# POWER.net
KiCad netlist of a schematic drawn in Altium Designer
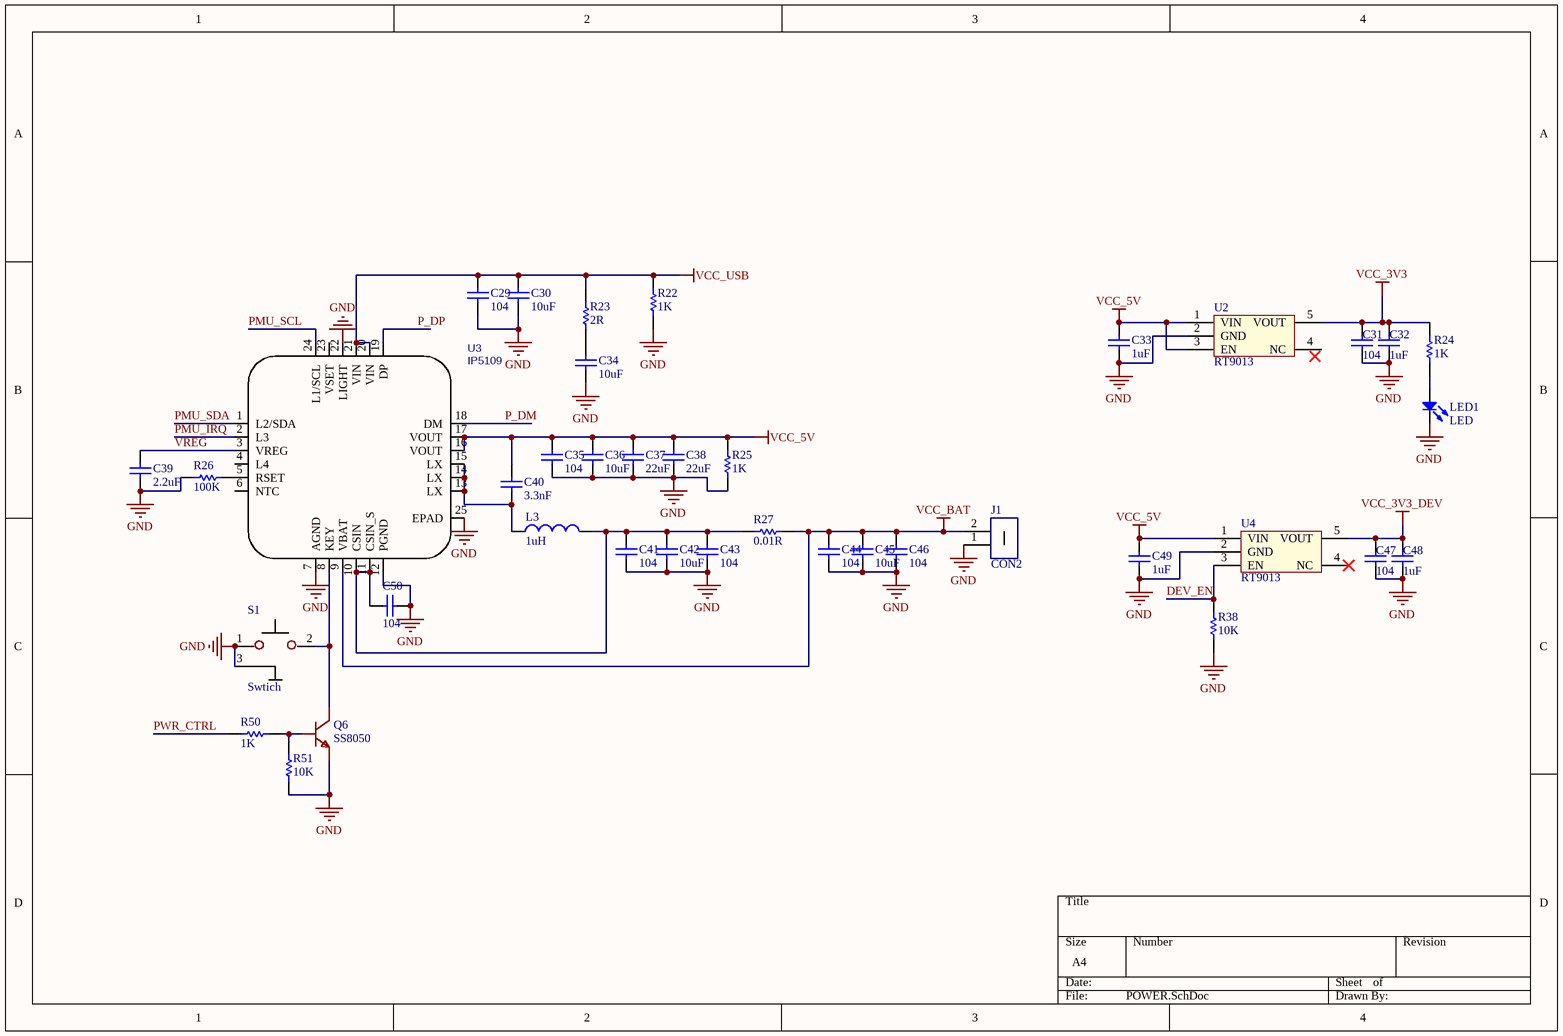
[diagram p0: POWER.SchDoc]

(export (version "E")
  (design (tool "Eeschema 10.0.6"))
  (components
    (comp (ref "C29")
      (value "104")
      (footprint "C 0603")
      (description "Capacitor")
      (libsource (lib "Miscellaneous Devices") (part "Cap"))
    )
    (comp (ref "C30")
      (value "10uF")
      (footprint "C 0603")
      (description "Capacitor")
      (libsource (lib "Miscellaneous Devices") (part "Cap"))
    )
    (comp (ref "C31") (value "104") (footprint "C 0603") (libsource (lib "Sheet") (part "CAP")))
    (comp (ref "C32") (value "1uF") (footprint "C 0603") (libsource (lib "Sheet") (part "CAP")))
    (comp (ref "C33") (value "1uF") (footprint "C 0603") (libsource (lib "Sheet") (part "CAP")))
    (comp (ref "C34")
      (value "10uF")
      (footprint "C 0603")
      (description "Capacitor")
      (libsource (lib "Miscellaneous Devices") (part "Cap"))
    )
    (comp (ref "C35")
      (value "104")
      (footprint "C 0603")
      (description "Capacitor")
      (libsource (lib "Miscellaneous Devices") (part "Cap"))
    )
    (comp (ref "C36")
      (value "10uF")
      (footprint "C 0603")
      (description "Capacitor")
      (libsource (lib "Miscellaneous Devices") (part "Cap"))
    )
    (comp (ref "C37")
      (value "22uF")
      (footprint "C 0603")
      (description "Capacitor")
      (libsource (lib "Miscellaneous Devices") (part "Cap"))
    )
    (comp (ref "C38")
      (value "22uF")
      (footprint "C 0603")
      (description "Capacitor")
      (libsource (lib "Miscellaneous Devices") (part "Cap"))
    )
    (comp (ref "C39") (value "2.2uF") (footprint "C 0603") (libsource (lib "Sheet") (part "CAP")))
    (comp (ref "C40")
      (value "3.3nF")
      (footprint "C 0603")
      (description "Capacitor")
      (libsource (lib "Miscellaneous Devices") (part "Cap"))
    )
    (comp (ref "C41")
      (value "104")
      (footprint "C 0603")
      (description "Capacitor")
      (libsource (lib "Miscellaneous Devices") (part "Cap"))
    )
    (comp (ref "C42")
      (value "10uF")
      (footprint "C 0603")
      (description "Capacitor")
      (libsource (lib "Miscellaneous Devices") (part "Cap"))
    )
    (comp (ref "C43")
      (value "104")
      (footprint "C 0603")
      (description "Capacitor")
      (libsource (lib "Miscellaneous Devices") (part "Cap"))
    )
    (comp (ref "C44")
      (value "104")
      (footprint "C 0603")
      (description "Capacitor")
      (libsource (lib "Miscellaneous Devices") (part "Cap"))
    )
    (comp (ref "C45")
      (value "10uF")
      (footprint "C 0603")
      (description "Capacitor")
      (libsource (lib "Miscellaneous Devices") (part "Cap"))
    )
    (comp (ref "C46")
      (value "104")
      (footprint "C 0603")
      (description "Capacitor")
      (libsource (lib "Miscellaneous Devices") (part "Cap"))
    )
    (comp (ref "C47") (value "104") (footprint "C 0603") (libsource (lib "Sheet") (part "CAP")))
    (comp (ref "C48") (value "1uF") (footprint "C 0603") (libsource (lib "Sheet") (part "CAP")))
    (comp (ref "C49") (value "1uF") (footprint "C 0603") (libsource (lib "Sheet") (part "CAP")))
    (comp (ref "C50")
      (value "104")
      (footprint "C 0603")
      (description "Capacitor")
      (libsource (lib "Miscellaneous Devices") (part "Cap"))
    )
    (comp (ref "J1") (value "CON2") (footprint "XH-2P-SMD") (libsource (lib "Sheet") (part "CON2")))
    (comp (ref "L3")
      (value "1uH")
      (footprint "L_7*7")
      (description "Inductor")
      (libsource (lib "Miscellaneous Devices") (part "Inductor"))
    )
    (comp (ref "LED1") (value "LED") (footprint "0603_LED") (libsource (lib "squ-guiboard") (part "LED")))
    (comp (ref "Q6") (value "SS8050") (footprint "SOT-23") (libsource (lib "Sheet") (part "NPN")))
    (comp (ref "R22") (value "1K") (footprint "R 0603") (libsource (lib "Sheet") (part "RES")))
    (comp (ref "R23") (value "2R") (footprint "R 0603") (libsource (lib "Sheet") (part "RES")))
    (comp (ref "R24") (value "1K") (footprint "R 0603") (libsource (lib "Sheet") (part "RES")))
    (comp (ref "R25") (value "1K") (footprint "R 0603") (libsource (lib "Sheet") (part "RES")))
    (comp (ref "R26") (value "100K") (footprint "R 0603") (libsource (lib "Sheet") (part "RES")))
    (comp (ref "R27") (value "0.01R") (footprint "R 1206") (libsource (lib "Sheet") (part "RES")))
    (comp (ref "R38") (value "10K") (footprint "R 0603") (libsource (lib "Sheet") (part "RES")))
    (comp (ref "R50") (value "1K") (footprint "R 0603") (libsource (lib "Sheet") (part "RES")))
    (comp (ref "R51") (value "10K") (footprint "R 0603") (libsource (lib "Sheet") (part "RES")))
    (comp (ref "S1") (value "Swtich") (footprint "SW3*6") (libsource (lib "Sheet") (part "Switch-th")))
    (comp (ref "U2")
      (value "RT9013")
      (footprint "SOT23-5")
      (description "500mA低压差LDO")
      (libsource (lib "squ-guiboard") (part "RT9013"))
    )
    (comp (ref "U3")
      (value "IP5109")
      (footprint "QFN-24")
      (fields (field (name "BOM_SUPPLIER PART") "C181699") (field (name "CONTRIBUTOR") "LCSC"))
      (libsource (lib "Sheet") (part "IP5109"))
    )
    (comp (ref "U4")
      (value "RT9013")
      (footprint "SOT23-5")
      (description "500mA低压差LDO")
      (libsource (lib "squ-guiboard") (part "RT9013"))
    )
  )
  (nets
    (net (code "1") (name "/DEV_EN") (class "Default")
      (node (ref "R38") (pin "2") (pinfunction "2_2") (pintype "passive"))
      (node (ref "U4") (pin "3") (pinfunction "EN_3") (pintype "passive"))
    )
    (net (code "2") (name "/PMU_IRQ") (class "Default")
      (node (ref "U3") (pin "2") (pinfunction "L3_2") (pintype "passive"))
    )
    (net (code "3") (name "/PMU_SCL") (class "Default")
      (node (ref "U3") (pin "24") (pinfunction "L1/SCL_24") (pintype "passive"))
    )
    (net (code "4") (name "/PMU_SDA") (class "Default")
      (node (ref "U3") (pin "1") (pinfunction "L2/SDA_1") (pintype "passive"))
    )
    (net (code "5") (name "/PWR_CTRL") (class "Default")
      (node (ref "R50") (pin "2") (pinfunction "2_2") (pintype "passive"))
    )
    (net (code "6") (name "/P_DM") (class "Default")
      (node (ref "U3") (pin "18") (pinfunction "DM_18") (pintype "passive"))
    )
    (net (code "7") (name "/P_DP") (class "Default")
      (node (ref "U3") (pin "19") (pinfunction "DP_19") (pintype "passive"))
    )
    (net (code "8") (name "/VREG") (class "Default")
      (node (ref "C39") (pin "2") (pinfunction "2_2") (pintype "passive"))
      (node (ref "U3") (pin "3") (pinfunction "VREG_3") (pintype "passive"))
    )
    (net (code "9") (name "GND") (class "Default")
      (node (ref "C29") (pin "1") (pinfunction "1_1") (pintype "passive"))
      (node (ref "C30") (pin "1") (pinfunction "1_1") (pintype "passive"))
      (node (ref "C31") (pin "1") (pinfunction "1_1") (pintype "passive"))
      (node (ref "C32") (pin "1") (pinfunction "1_1") (pintype "passive"))
      (node (ref "C33") (pin "1") (pinfunction "1_1") (pintype "passive"))
      (node (ref "C34") (pin "1") (pinfunction "1_1") (pintype "passive"))
      (node (ref "C35") (pin "1") (pinfunction "1_1") (pintype "passive"))
      (node (ref "C36") (pin "1") (pinfunction "1_1") (pintype "passive"))
      (node (ref "C37") (pin "1") (pinfunction "1_1") (pintype "passive"))
      (node (ref "C38") (pin "1") (pinfunction "1_1") (pintype "passive"))
      (node (ref "C39") (pin "1") (pinfunction "1_1") (pintype "passive"))
      (node (ref "C41") (pin "1") (pinfunction "1_1") (pintype "passive"))
      (node (ref "C42") (pin "1") (pinfunction "1_1") (pintype "passive"))
      (node (ref "C43") (pin "1") (pinfunction "1_1") (pintype "passive"))
      (node (ref "C44") (pin "1") (pinfunction "1_1") (pintype "passive"))
      (node (ref "C45") (pin "1") (pinfunction "1_1") (pintype "passive"))
      (node (ref "C46") (pin "1") (pinfunction "1_1") (pintype "passive"))
      (node (ref "C47") (pin "1") (pinfunction "1_1") (pintype "passive"))
      (node (ref "C48") (pin "1") (pinfunction "1_1") (pintype "passive"))
      (node (ref "C49") (pin "1") (pinfunction "1_1") (pintype "passive"))
      (node (ref "C50") (pin "1") (pinfunction "1_1") (pintype "passive"))
      (node (ref "J1") (pin "1") (pinfunction "1_1") (pintype "passive"))
      (node (ref "LED1") (pin "2") (pinfunction "K_2") (pintype "passive"))
      (node (ref "Q6") (pin "2") (pinfunction "E_2") (pintype "passive"))
      (node (ref "R22") (pin "1") (pinfunction "1_1") (pintype "passive"))
      (node (ref "R25") (pin "1") (pinfunction "1_1") (pintype "passive"))
      (node (ref "R26") (pin "2") (pinfunction "2_2") (pintype "passive"))
      (node (ref "R38") (pin "1") (pinfunction "1_1") (pintype "passive"))
      (node (ref "R51") (pin "1") (pinfunction "1_1") (pintype "passive"))
      (node (ref "S1") (pin "1") (pinfunction "1_1") (pintype "passive"))
      (node (ref "S1") (pin "3") (pinfunction "3_3") (pintype "passive"))
      (node (ref "U2") (pin "2") (pinfunction "GND_2") (pintype "passive"))
      (node (ref "U3") (pin "12") (pinfunction "PGND_12") (pintype "passive"))
      (node (ref "U3") (pin "22") (pinfunction "LIGHT_22") (pintype "passive"))
      (node (ref "U3") (pin "25") (pinfunction "EPAD_25") (pintype "passive"))
      (node (ref "U3") (pin "7") (pinfunction "AGND_7") (pintype "passive"))
      (node (ref "U4") (pin "2") (pinfunction "GND_2") (pintype "passive"))
    )
    (net (code "10") (name "Net-(C34-Pad2)") (class "Default")
      (node (ref "C34") (pin "2") (pinfunction "2_2") (pintype "passive"))
      (node (ref "R23") (pin "1") (pinfunction "1_1") (pintype "passive"))
    )
    (net (code "11") (name "Net-(C40-Pad1)") (class "Default")
      (node (ref "C40") (pin "1") (pinfunction "1_1") (pintype "passive"))
      (node (ref "L3") (pin "1") (pinfunction "1_1") (pintype "passive"))
      (node (ref "U3") (pin "13") (pinfunction "LX_13") (pintype "passive"))
      (node (ref "U3") (pin "14") (pinfunction "LX_14") (pintype "passive"))
      (node (ref "U3") (pin "15") (pinfunction "LX_15") (pintype "passive"))
    )
    (net (code "12") (name "Net-(LED1-A)") (class "Default")
      (node (ref "LED1") (pin "1") (pinfunction "A_1") (pintype "passive"))
      (node (ref "R24") (pin "1") (pinfunction "1_1") (pintype "passive"))
    )
    (net (code "13") (name "Net-(Q6-B)") (class "Default")
      (node (ref "Q6") (pin "1") (pinfunction "B_1") (pintype "passive"))
      (node (ref "R50") (pin "1") (pinfunction "1_1") (pintype "passive"))
      (node (ref "R51") (pin "2") (pinfunction "2_2") (pintype "passive"))
    )
    (net (code "14") (name "Net-(Q6-C)") (class "Default")
      (node (ref "Q6") (pin "3") (pinfunction "C_3") (pintype "passive"))
      (node (ref "S1") (pin "2") (pinfunction "2_2") (pintype "passive"))
      (node (ref "U3") (pin "8") (pinfunction "KEY_8") (pintype "passive"))
    )
    (net (code "15") (name "Net-(U3-CSIN)") (class "Default")
      (node (ref "C41") (pin "2") (pinfunction "2_2") (pintype "passive"))
      (node (ref "C42") (pin "2") (pinfunction "2_2") (pintype "passive"))
      (node (ref "C43") (pin "2") (pinfunction "2_2") (pintype "passive"))
      (node (ref "C50") (pin "2") (pinfunction "2_2") (pintype "passive"))
      (node (ref "L3") (pin "2") (pinfunction "2_2") (pintype "passive"))
      (node (ref "R27") (pin "2") (pinfunction "2_2") (pintype "passive"))
      (node (ref "U3") (pin "10") (pinfunction "CSIN_10") (pintype "passive"))
      (node (ref "U3") (pin "11") (pinfunction "CSIN_S_11") (pintype "passive"))
    )
    (net (code "16") (name "Net-(U3-RSET)") (class "Default")
      (node (ref "R26") (pin "1") (pinfunction "1_1") (pintype "passive"))
      (node (ref "U3") (pin "5") (pinfunction "RSET_5") (pintype "passive"))
    )
    (net (code "17") (name "VCC_3V3") (class "Default")
      (node (ref "C31") (pin "2") (pinfunction "2_2") (pintype "passive"))
      (node (ref "C32") (pin "2") (pinfunction "2_2") (pintype "passive"))
      (node (ref "R24") (pin "2") (pinfunction "2_2") (pintype "passive"))
      (node (ref "U2") (pin "5") (pinfunction "VOUT_5") (pintype "passive"))
    )
    (net (code "18") (name "VCC_3V3_DEV") (class "Default")
      (node (ref "C47") (pin "2") (pinfunction "2_2") (pintype "passive"))
      (node (ref "C48") (pin "2") (pinfunction "2_2") (pintype "passive"))
      (node (ref "U4") (pin "5") (pinfunction "VOUT_5") (pintype "passive"))
    )
    (net (code "19") (name "VCC_5V") (class "Default")
      (node (ref "C33") (pin "2") (pinfunction "2_2") (pintype "passive"))
      (node (ref "C35") (pin "2") (pinfunction "2_2") (pintype "passive"))
      (node (ref "C36") (pin "2") (pinfunction "2_2") (pintype "passive"))
      (node (ref "C37") (pin "2") (pinfunction "2_2") (pintype "passive"))
      (node (ref "C38") (pin "2") (pinfunction "2_2") (pintype "passive"))
      (node (ref "C40") (pin "2") (pinfunction "2_2") (pintype "passive"))
      (node (ref "C49") (pin "2") (pinfunction "2_2") (pintype "passive"))
      (node (ref "R25") (pin "2") (pinfunction "2_2") (pintype "passive"))
      (node (ref "U2") (pin "1") (pinfunction "VIN_1") (pintype "passive"))
      (node (ref "U2") (pin "3") (pinfunction "EN_3") (pintype "passive"))
      (node (ref "U3") (pin "16") (pinfunction "VOUT_16") (pintype "passive"))
      (node (ref "U3") (pin "17") (pinfunction "VOUT_17") (pintype "passive"))
      (node (ref "U4") (pin "1") (pinfunction "VIN_1") (pintype "passive"))
    )
    (net (code "20") (name "VCC_BAT") (class "Default")
      (node (ref "C44") (pin "2") (pinfunction "2_2") (pintype "passive"))
      (node (ref "C45") (pin "2") (pinfunction "2_2") (pintype "passive"))
      (node (ref "C46") (pin "2") (pinfunction "2_2") (pintype "passive"))
      (node (ref "J1") (pin "2") (pinfunction "2_2") (pintype "passive"))
      (node (ref "R27") (pin "1") (pinfunction "1_1") (pintype "passive"))
      (node (ref "U3") (pin "9") (pinfunction "VBAT_9") (pintype "passive"))
    )
    (net (code "21") (name "VCC_USB") (class "Default")
      (node (ref "C29") (pin "2") (pinfunction "2_2") (pintype "passive"))
      (node (ref "C30") (pin "2") (pinfunction "2_2") (pintype "passive"))
      (node (ref "R22") (pin "2") (pinfunction "2_2") (pintype "passive"))
      (node (ref "R23") (pin "2") (pinfunction "2_2") (pintype "passive"))
      (node (ref "U3") (pin "20") (pinfunction "VIN_20") (pintype "passive"))
      (node (ref "U3") (pin "21") (pinfunction "VIN_21") (pintype "passive"))
    )
    (net (code "22") (name "unconnected-(U2-NC-Pad4)") (class "Default")
      (node (ref "U2") (pin "4") (pinfunction "NC_4") (pintype "passive"))
    )
    (net (code "23") (name "unconnected-(U3-L4-Pad4)") (class "Default")
      (node (ref "U3") (pin "4") (pinfunction "L4_4") (pintype "passive"))
    )
    (net (code "24") (name "unconnected-(U3-NTC-Pad6)") (class "Default")
      (node (ref "U3") (pin "6") (pinfunction "NTC_6") (pintype "passive"))
    )
    (net (code "25") (name "unconnected-(U3-VSET-Pad23)") (class "Default")
      (node (ref "U3") (pin "23") (pinfunction "VSET_23") (pintype "passive"))
    )
    (net (code "26") (name "unconnected-(U4-NC-Pad4)") (class "Default")
      (node (ref "U4") (pin "4") (pinfunction "NC_4") (pintype "passive+no_connect"))
    )
  )
)
